# Optical_Spark_V2_0.net
KiCad netlist of a schematic drawn in EAGLE
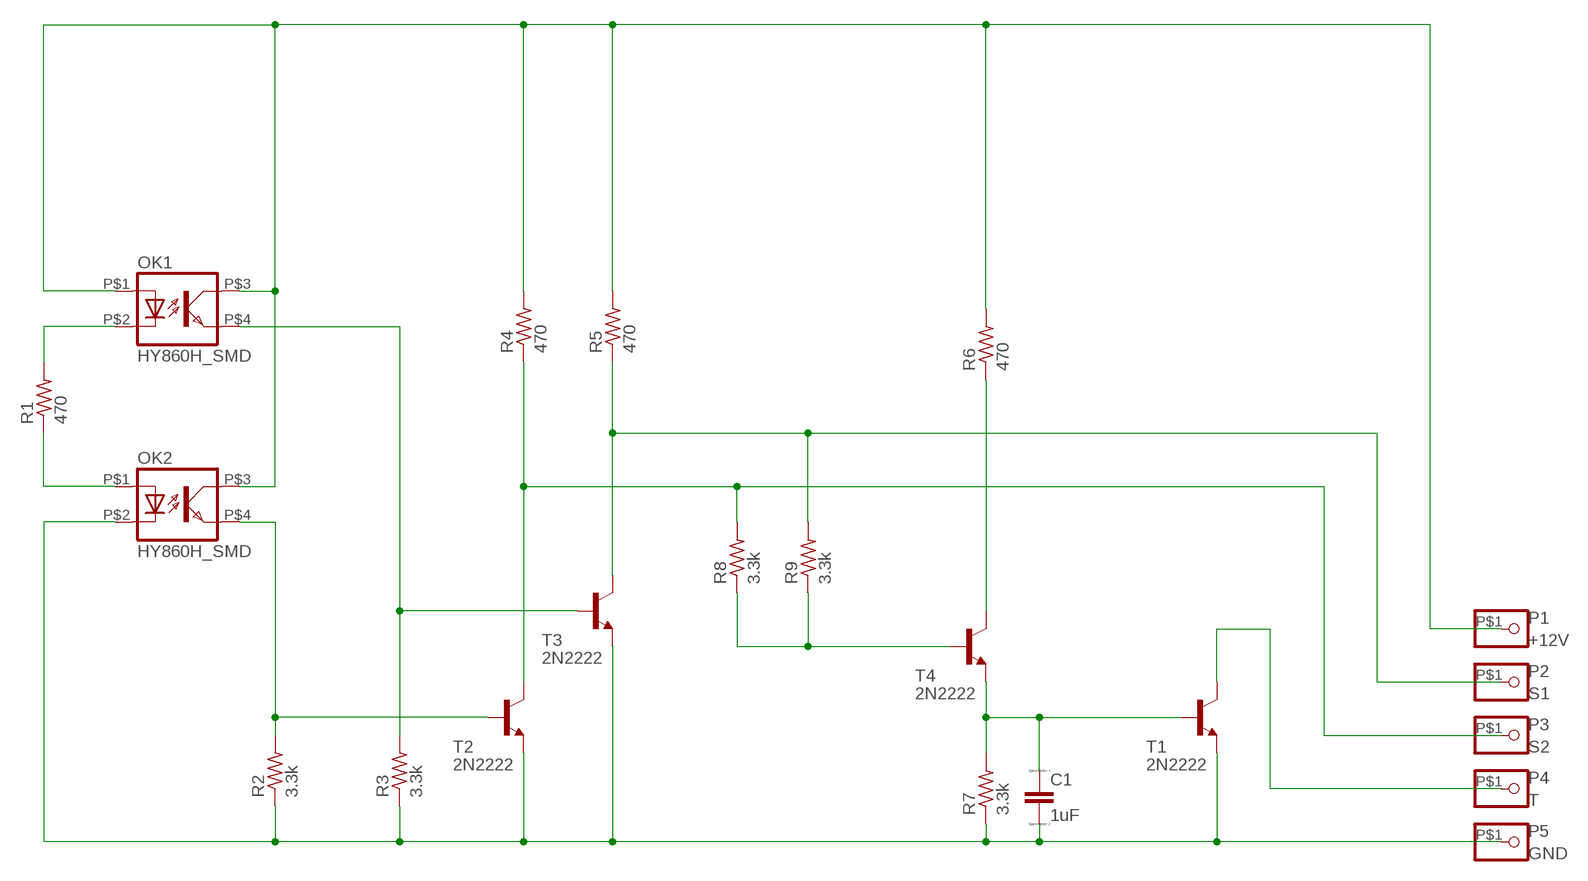
[diagram p0: schematic, sheet 1]

(export (version "E")
  (design (tool "Eeschema 10.0.6"))
  (components
    (comp (ref "C1")
      (value "1uF")
      (footprint "eagle-import:SMALLCAP_THT_SMD")
      (libsource (lib "eagle-import") (part "SMALLCAP_THT_SMD"))
    )
    (comp (ref "OK1")
      (value "HY860H_SMD")
      (footprint "eagle-import:HY860H_SMD")
      (libsource (lib "eagle-import") (part "HY860H_SMD"))
    )
    (comp (ref "OK2")
      (value "HY860H_SMD")
      (footprint "eagle-import:HY860H_SMD")
      (libsource (lib "eagle-import") (part "HY860H_SMD"))
    )
    (comp (ref "P1")
      (value "+12V")
      (footprint "eagle-import:PAD")
      (libsource (lib "eagle-import") (part "PAD"))
    )
    (comp (ref "P2")
      (value "S1")
      (footprint "eagle-import:PAD")
      (libsource (lib "eagle-import") (part "PAD"))
    )
    (comp (ref "P3")
      (value "S2")
      (footprint "eagle-import:PAD")
      (libsource (lib "eagle-import") (part "PAD"))
    )
    (comp (ref "P4") (value "T") (footprint "eagle-import:PAD") (libsource (lib "eagle-import") (part "PAD")))
    (comp (ref "P5")
      (value "GND")
      (footprint "eagle-import:PAD")
      (libsource (lib "eagle-import") (part "PAD"))
    )
    (comp (ref "R1")
      (value "470")
      (footprint "eagle-import:0.25W_THT_SMD")
      (libsource (lib "eagle-import") (part "0.25W_THT_SMD"))
    )
    (comp (ref "R2")
      (value "3.3k")
      (footprint "eagle-import:0.25W_THT_SMD_SMALL")
      (libsource (lib "eagle-import") (part "0.25W_THT_SMD_SMALL"))
    )
    (comp (ref "R3")
      (value "3.3k")
      (footprint "eagle-import:0.25W_THT_SMD_SMALL")
      (libsource (lib "eagle-import") (part "0.25W_THT_SMD_SMALL"))
    )
    (comp (ref "R4")
      (value "470")
      (footprint "eagle-import:0.25W_THT_SMD")
      (libsource (lib "eagle-import") (part "0.25W_THT_SMD"))
    )
    (comp (ref "R5")
      (value "470")
      (footprint "eagle-import:0.25W_THT_SMD")
      (libsource (lib "eagle-import") (part "0.25W_THT_SMD"))
    )
    (comp (ref "R6")
      (value "470")
      (footprint "eagle-import:0.25W_THT_SMD")
      (libsource (lib "eagle-import") (part "0.25W_THT_SMD"))
    )
    (comp (ref "R7")
      (value "3.3k")
      (footprint "eagle-import:0.25W_THT_SMD_SMALL")
      (libsource (lib "eagle-import") (part "0.25W_THT_SMD_SMALL"))
    )
    (comp (ref "R8")
      (value "3.3k")
      (footprint "eagle-import:0.25W_THT_SMD_SMALL")
      (libsource (lib "eagle-import") (part "0.25W_THT_SMD_SMALL"))
    )
    (comp (ref "R9")
      (value "3.3k")
      (footprint "eagle-import:0.25W_THT_SMD_SMALL")
      (libsource (lib "eagle-import") (part "0.25W_THT_SMD_SMALL"))
    )
    (comp (ref "T1")
      (value "2N2222")
      (footprint "eagle-import:NPN_THT_SMD_EBC")
      (libsource (lib "eagle-import") (part "NPN_THT_SMD_EBC"))
    )
    (comp (ref "T2")
      (value "2N2222")
      (footprint "eagle-import:NPN_THT_SMD_EBC")
      (libsource (lib "eagle-import") (part "NPN_THT_SMD_EBC"))
    )
    (comp (ref "T3")
      (value "2N2222")
      (footprint "eagle-import:NPN_THT_SMD_EBC")
      (libsource (lib "eagle-import") (part "NPN_THT_SMD_EBC"))
    )
    (comp (ref "T4")
      (value "2N2222")
      (footprint "eagle-import:NPN_THT_SMD_EBC")
      (libsource (lib "eagle-import") (part "NPN_THT_SMD_EBC"))
    )
  )
  (nets
    (net (code "1") (name "Net-(C1-1)") (class "Default")
      (node (ref "C1") (pin "P$1") (pinfunction "1_P$1") (pintype "passive"))
      (node (ref "R7") (pin "P$2") (pinfunction "2_P$2") (pintype "passive"))
      (node (ref "T1") (pin "P$2") (pinfunction "B_P$2") (pintype "passive"))
      (node (ref "T4") (pin "P$1") (pinfunction "E_P$1") (pintype "passive"))
    )
    (net (code "2") (name "Net-(C1-2)") (class "Default")
      (node (ref "C1") (pin "P$2") (pinfunction "2_P$2") (pintype "passive"))
      (node (ref "OK2") (pin "P$2") (pinfunction "C_P$2") (pintype "passive"))
      (node (ref "P5") (pin "P$1") (pinfunction "1_P$1") (pintype "passive"))
      (node (ref "R2") (pin "P$1") (pinfunction "1_P$1") (pintype "passive"))
      (node (ref "R3") (pin "P$1") (pinfunction "1_P$1") (pintype "passive"))
      (node (ref "R7") (pin "P$1") (pinfunction "1_P$1") (pintype "passive"))
      (node (ref "T1") (pin "P$1") (pinfunction "E_P$1") (pintype "passive"))
      (node (ref "T2") (pin "P$1") (pinfunction "E_P$1") (pintype "passive"))
      (node (ref "T3") (pin "P$1") (pinfunction "E_P$1") (pintype "passive"))
    )
    (net (code "3") (name "Net-(OK1-A)") (class "Default")
      (node (ref "OK1") (pin "P$1") (pinfunction "A_P$1") (pintype "passive"))
      (node (ref "OK1") (pin "P$3") (pinfunction "COL_P$3") (pintype "passive"))
      (node (ref "OK2") (pin "P$3") (pinfunction "COL_P$3") (pintype "passive"))
      (node (ref "P1") (pin "P$1") (pinfunction "1_P$1") (pintype "passive"))
      (node (ref "R4") (pin "P$2") (pinfunction "2_P$2") (pintype "passive"))
      (node (ref "R5") (pin "P$2") (pinfunction "2_P$2") (pintype "passive"))
      (node (ref "R6") (pin "P$2") (pinfunction "2_P$2") (pintype "passive"))
    )
    (net (code "4") (name "Net-(OK1-C)") (class "Default")
      (node (ref "OK1") (pin "P$2") (pinfunction "C_P$2") (pintype "passive"))
      (node (ref "R1") (pin "P$2") (pinfunction "2_P$2") (pintype "passive"))
    )
    (net (code "5") (name "Net-(OK1-EMIT)") (class "Default")
      (node (ref "OK1") (pin "P$4") (pinfunction "EMIT_P$4") (pintype "passive"))
      (node (ref "R3") (pin "P$2") (pinfunction "2_P$2") (pintype "passive"))
      (node (ref "T3") (pin "P$2") (pinfunction "B_P$2") (pintype "passive"))
    )
    (net (code "6") (name "Net-(OK2-A)") (class "Default")
      (node (ref "OK2") (pin "P$1") (pinfunction "A_P$1") (pintype "passive"))
      (node (ref "R1") (pin "P$1") (pinfunction "1_P$1") (pintype "passive"))
    )
    (net (code "7") (name "Net-(OK2-EMIT)") (class "Default")
      (node (ref "OK2") (pin "P$4") (pinfunction "EMIT_P$4") (pintype "passive"))
      (node (ref "R2") (pin "P$2") (pinfunction "2_P$2") (pintype "passive"))
      (node (ref "T2") (pin "P$2") (pinfunction "B_P$2") (pintype "passive"))
    )
    (net (code "8") (name "Net-(P2-1)") (class "Default")
      (node (ref "P2") (pin "P$1") (pinfunction "1_P$1") (pintype "passive"))
      (node (ref "R5") (pin "P$1") (pinfunction "1_P$1") (pintype "passive"))
      (node (ref "R9") (pin "P$2") (pinfunction "2_P$2") (pintype "passive"))
      (node (ref "T3") (pin "P$3") (pinfunction "C_P$3") (pintype "passive"))
    )
    (net (code "9") (name "Net-(P3-1)") (class "Default")
      (node (ref "P3") (pin "P$1") (pinfunction "1_P$1") (pintype "passive"))
      (node (ref "R4") (pin "P$1") (pinfunction "1_P$1") (pintype "passive"))
      (node (ref "R8") (pin "P$2") (pinfunction "2_P$2") (pintype "passive"))
      (node (ref "T2") (pin "P$3") (pinfunction "C_P$3") (pintype "passive"))
    )
    (net (code "10") (name "Net-(P4-1)") (class "Default")
      (node (ref "P4") (pin "P$1") (pinfunction "1_P$1") (pintype "passive"))
      (node (ref "T1") (pin "P$3") (pinfunction "C_P$3") (pintype "passive"))
    )
    (net (code "11") (name "Net-(R6-1)") (class "Default")
      (node (ref "R6") (pin "P$1") (pinfunction "1_P$1") (pintype "passive"))
      (node (ref "T4") (pin "P$3") (pinfunction "C_P$3") (pintype "passive"))
    )
    (net (code "12") (name "Net-(R8-1)") (class "Default")
      (node (ref "R8") (pin "P$1") (pinfunction "1_P$1") (pintype "passive"))
      (node (ref "R9") (pin "P$1") (pinfunction "1_P$1") (pintype "passive"))
      (node (ref "T4") (pin "P$2") (pinfunction "B_P$2") (pintype "passive"))
    )
  )
)
